# FPGA_ram.net
KiCad netlist of a schematic drawn in Altium Designer
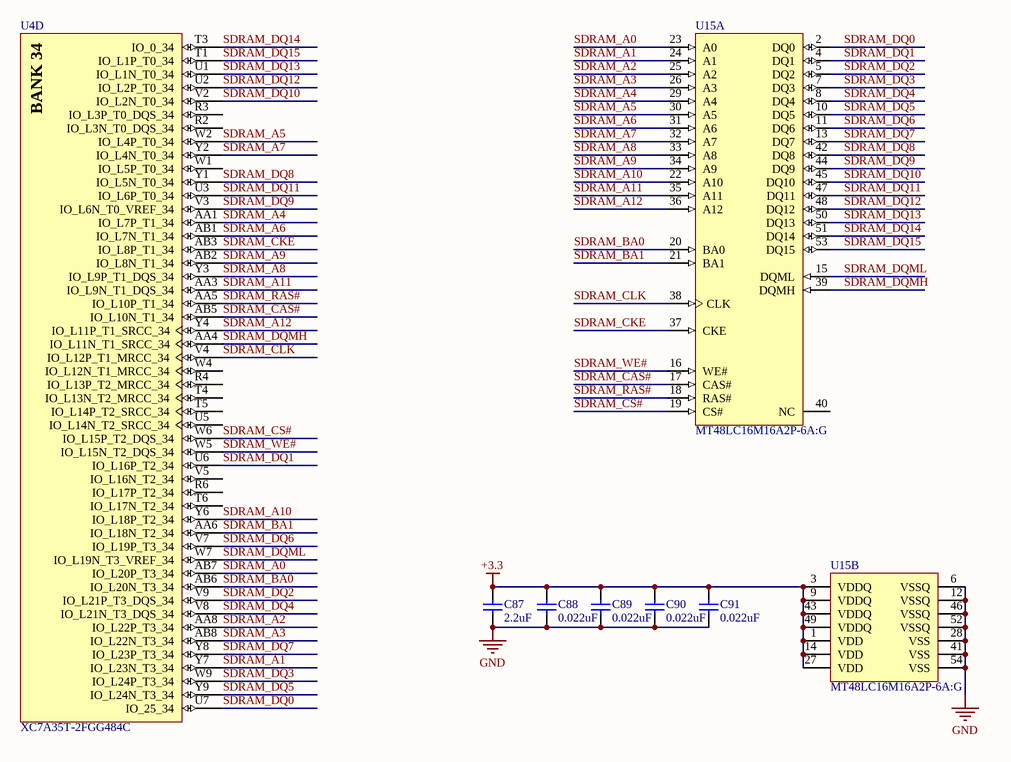
[diagram p0: FPGA ram.SchDoc]

(export (version "E")
  (design (tool "Eeschema 10.0.6"))
  (components
    (comp (ref "C87")
      (value "2.2uF")
      (footprint "CAPC1005X06L")
      (description "CAP CER 2.2UF 10V X5R 0402")
      (fields
        (field (name "PARTNUMBER") "GRM155R61A225KE95D")
        (field (name "DIGI-KEY PART NUMBER") "490-10451-1-ND")
      )
      (libsource (lib "cap_murata") (part "CAPACITOR"))
    )
    (comp (ref "C88")
      (value "0.022uF")
      (footprint "CAPC1005X06L")
      (description "CAP CER 0.022UF 10V X5R 0402")
      (fields
        (field (name "PARTNUMBER") "GRM155R61A223KA01D")
        (field (name "DIGI-KEY PART NUMBER") "490-6302-1-ND")
      )
      (libsource (lib "cap_murata") (part "CAPACITOR"))
    )
    (comp (ref "C89")
      (value "0.022uF")
      (footprint "CAPC1005X06L")
      (description "CAP CER 0.022UF 10V X5R 0402")
      (fields
        (field (name "PARTNUMBER") "GRM155R61A223KA01D")
        (field (name "DIGI-KEY PART NUMBER") "490-6302-1-ND")
      )
      (libsource (lib "cap_murata") (part "CAPACITOR"))
    )
    (comp (ref "C90")
      (value "0.022uF")
      (footprint "CAPC1005X06L")
      (description "CAP CER 0.022UF 10V X5R 0402")
      (fields
        (field (name "PARTNUMBER") "GRM155R61A223KA01D")
        (field (name "DIGI-KEY PART NUMBER") "490-6302-1-ND")
      )
      (libsource (lib "cap_murata") (part "CAPACITOR"))
    )
    (comp (ref "C91")
      (value "0.022uF")
      (footprint "CAPC1005X06L")
      (description "CAP CER 0.022UF 10V X5R 0402")
      (fields
        (field (name "PARTNUMBER") "GRM155R61A223KA01D")
        (field (name "DIGI-KEY PART NUMBER") "490-6302-1-ND")
      )
      (libsource (lib "cap_murata") (part "CAPACITOR"))
    )
    (comp (ref "U4")
      (value "XC7A35T-2FGG484C")
      (footprint "FGG484")
      (description "Artix-7 FPGA, 250 User I/Os, 4 GTP, 484-Ball BGA, Speed Grade 2, Commercial Grade, Pb-Free")
      (fields (field (name "MANUFACTURER") "Xilinx"))
      (libsource (lib "Altium Content Vault") (part "XLNX-XC7A35T-FGG484"))
    )
    (comp (ref "U15")
      (value "MT48LC16M16A2P-6A:G")
      (footprint "MICT-TG-54_M")
      (description "256 Mb PC133 SDR SDRAM, 16 Mb x 16, 3 to 3.6 V, 0 to 70 degC, 54-Pin TSOP (TG), Pb-Free")
      (fields (field (name "MANUFACTURER") "Micron"))
      (libsource (lib "Altium Content Vault") (part "MICT-MT48LC16M16A2P-54"))
    )
  )
  (nets
    (net (code "1") (name "+3.3") (class "Default")
      (node (ref "C87") (pin "1") (pinfunction "1_1") (pintype "passive"))
      (node (ref "C88") (pin "1") (pinfunction "1_1") (pintype "passive"))
      (node (ref "C89") (pin "1") (pinfunction "1_1") (pintype "passive"))
      (node (ref "C90") (pin "1") (pinfunction "1_1") (pintype "passive"))
      (node (ref "C91") (pin "1") (pinfunction "1_1") (pintype "passive"))
      (node (ref "U15") (pin "1") (pinfunction "VDD_1") (pintype "power_in"))
      (node (ref "U15") (pin "14") (pinfunction "VDD_14") (pintype "power_in"))
      (node (ref "U15") (pin "27") (pinfunction "VDD_27") (pintype "power_in"))
      (node (ref "U15") (pin "3") (pinfunction "VDDQ_3") (pintype "power_in"))
      (node (ref "U15") (pin "43") (pinfunction "VDDQ_43") (pintype "power_in"))
      (node (ref "U15") (pin "49") (pinfunction "VDDQ_49") (pintype "power_in"))
      (node (ref "U15") (pin "9") (pinfunction "VDDQ_9") (pintype "power_in"))
    )
    (net (code "2") (name "/SDRAM_A0") (class "Default")
      (node (ref "U15") (pin "23") (pinfunction "A0_23") (pintype "input"))
      (node (ref "U4") (pin "AB7") (pinfunction "IO_L20P_T3_34_AB7") (pintype "bidirectional"))
    )
    (net (code "3") (name "/SDRAM_A1") (class "Default")
      (node (ref "U15") (pin "24") (pinfunction "A1_24") (pintype "input"))
      (node (ref "U4") (pin "Y7") (pinfunction "IO_L23N_T3_34_Y7") (pintype "bidirectional"))
    )
    (net (code "4") (name "/SDRAM_A2") (class "Default")
      (node (ref "U15") (pin "25") (pinfunction "A2_25") (pintype "input"))
      (node (ref "U4") (pin "AA8") (pinfunction "IO_L22P_T3_34_AA8") (pintype "bidirectional"))
    )
    (net (code "5") (name "/SDRAM_A3") (class "Default")
      (node (ref "U15") (pin "26") (pinfunction "A3_26") (pintype "input"))
      (node (ref "U4") (pin "AB8") (pinfunction "IO_L22N_T3_34_AB8") (pintype "bidirectional"))
    )
    (net (code "6") (name "/SDRAM_A4") (class "Default")
      (node (ref "U15") (pin "29") (pinfunction "A4_29") (pintype "input"))
      (node (ref "U4") (pin "AA1") (pinfunction "IO_L7P_T1_34_AA1") (pintype "bidirectional"))
    )
    (net (code "7") (name "/SDRAM_A5") (class "Default")
      (node (ref "U15") (pin "30") (pinfunction "A5_30") (pintype "input"))
      (node (ref "U4") (pin "W2") (pinfunction "IO_L4P_T0_34_W2") (pintype "bidirectional"))
    )
    (net (code "8") (name "/SDRAM_A6") (class "Default")
      (node (ref "U15") (pin "31") (pinfunction "A6_31") (pintype "input"))
      (node (ref "U4") (pin "AB1") (pinfunction "IO_L7N_T1_34_AB1") (pintype "bidirectional"))
    )
    (net (code "9") (name "/SDRAM_A7") (class "Default")
      (node (ref "U15") (pin "32") (pinfunction "A7_32") (pintype "input"))
      (node (ref "U4") (pin "Y2") (pinfunction "IO_L4N_T0_34_Y2") (pintype "bidirectional"))
    )
    (net (code "10") (name "/SDRAM_A8") (class "Default")
      (node (ref "U15") (pin "33") (pinfunction "A8_33") (pintype "input"))
      (node (ref "U4") (pin "Y3") (pinfunction "IO_L9P_T1_DQS_34_Y3") (pintype "bidirectional"))
    )
    (net (code "11") (name "/SDRAM_A9") (class "Default")
      (node (ref "U15") (pin "34") (pinfunction "A9_34") (pintype "input"))
      (node (ref "U4") (pin "AB2") (pinfunction "IO_L8N_T1_34_AB2") (pintype "bidirectional"))
    )
    (net (code "12") (name "/SDRAM_A10") (class "Default")
      (node (ref "U15") (pin "22") (pinfunction "A10_22") (pintype "input"))
      (node (ref "U4") (pin "Y6") (pinfunction "IO_L18P_T2_34_Y6") (pintype "bidirectional"))
    )
    (net (code "13") (name "/SDRAM_A11") (class "Default")
      (node (ref "U15") (pin "35") (pinfunction "A11_35") (pintype "input"))
      (node (ref "U4") (pin "AA3") (pinfunction "IO_L9N_T1_DQS_34_AA3") (pintype "bidirectional"))
    )
    (net (code "14") (name "/SDRAM_A12") (class "Default")
      (node (ref "U15") (pin "36") (pinfunction "A12_36") (pintype "input"))
      (node (ref "U4") (pin "Y4") (pinfunction "IO_L11P_T1_SRCC_34_Y4") (pintype "bidirectional"))
    )
    (net (code "15") (name "/SDRAM_BA0") (class "Default")
      (node (ref "U15") (pin "20") (pinfunction "BA0_20") (pintype "input"))
      (node (ref "U4") (pin "AB6") (pinfunction "IO_L20N_T3_34_AB6") (pintype "bidirectional"))
    )
    (net (code "16") (name "/SDRAM_BA1") (class "Default")
      (node (ref "U15") (pin "21") (pinfunction "BA1_21") (pintype "input"))
      (node (ref "U4") (pin "AA6") (pinfunction "IO_L18N_T2_34_AA6") (pintype "bidirectional"))
    )
    (net (code "17") (name "/SDRAM_CAS#") (class "Default")
      (node (ref "U15") (pin "17") (pinfunction "CAS#_17") (pintype "input"))
      (node (ref "U4") (pin "AB5") (pinfunction "IO_L10N_T1_34_AB5") (pintype "bidirectional"))
    )
    (net (code "18") (name "/SDRAM_CKE") (class "Default")
      (node (ref "U15") (pin "37") (pinfunction "CKE_37") (pintype "input"))
      (node (ref "U4") (pin "AB3") (pinfunction "IO_L8P_T1_34_AB3") (pintype "bidirectional"))
    )
    (net (code "19") (name "/SDRAM_CLK") (class "Default")
      (node (ref "U15") (pin "38") (pinfunction "CLK_38") (pintype "input"))
      (node (ref "U4") (pin "V4") (pinfunction "IO_L12P_T1_MRCC_34_V4") (pintype "bidirectional"))
    )
    (net (code "20") (name "/SDRAM_CS#") (class "Default")
      (node (ref "U15") (pin "19") (pinfunction "CS#_19") (pintype "input"))
      (node (ref "U4") (pin "W6") (pinfunction "IO_L15P_T2_DQS_34_W6") (pintype "bidirectional"))
    )
    (net (code "21") (name "/SDRAM_DQ0") (class "Default")
      (node (ref "U15") (pin "2") (pinfunction "DQ0_2") (pintype "bidirectional"))
      (node (ref "U4") (pin "U7") (pinfunction "IO_25_34_U7") (pintype "bidirectional"))
    )
    (net (code "22") (name "/SDRAM_DQ1") (class "Default")
      (node (ref "U15") (pin "4") (pinfunction "DQ1_4") (pintype "bidirectional"))
      (node (ref "U4") (pin "U6") (pinfunction "IO_L16P_T2_34_U6") (pintype "bidirectional"))
    )
    (net (code "23") (name "/SDRAM_DQ2") (class "Default")
      (node (ref "U15") (pin "5") (pinfunction "DQ2_5") (pintype "bidirectional"))
      (node (ref "U4") (pin "V9") (pinfunction "IO_L21P_T3_DQS_34_V9") (pintype "bidirectional"))
    )
    (net (code "24") (name "/SDRAM_DQ3") (class "Default")
      (node (ref "U15") (pin "7") (pinfunction "DQ3_7") (pintype "bidirectional"))
      (node (ref "U4") (pin "W9") (pinfunction "IO_L24P_T3_34_W9") (pintype "bidirectional"))
    )
    (net (code "25") (name "/SDRAM_DQ4") (class "Default")
      (node (ref "U15") (pin "8") (pinfunction "DQ4_8") (pintype "bidirectional"))
      (node (ref "U4") (pin "V8") (pinfunction "IO_L21N_T3_DQS_34_V8") (pintype "bidirectional"))
    )
    (net (code "26") (name "/SDRAM_DQ5") (class "Default")
      (node (ref "U15") (pin "10") (pinfunction "DQ5_10") (pintype "bidirectional"))
      (node (ref "U4") (pin "Y9") (pinfunction "IO_L24N_T3_34_Y9") (pintype "bidirectional"))
    )
    (net (code "27") (name "/SDRAM_DQ6") (class "Default")
      (node (ref "U15") (pin "11") (pinfunction "DQ6_11") (pintype "bidirectional"))
      (node (ref "U4") (pin "V7") (pinfunction "IO_L19P_T3_34_V7") (pintype "bidirectional"))
    )
    (net (code "28") (name "/SDRAM_DQ7") (class "Default")
      (node (ref "U15") (pin "13") (pinfunction "DQ7_13") (pintype "bidirectional"))
      (node (ref "U4") (pin "Y8") (pinfunction "IO_L23P_T3_34_Y8") (pintype "bidirectional"))
    )
    (net (code "29") (name "/SDRAM_DQ8") (class "Default")
      (node (ref "U15") (pin "42") (pinfunction "DQ8_42") (pintype "bidirectional"))
      (node (ref "U4") (pin "Y1") (pinfunction "IO_L5N_T0_34_Y1") (pintype "bidirectional"))
    )
    (net (code "30") (name "/SDRAM_DQ9") (class "Default")
      (node (ref "U15") (pin "44") (pinfunction "DQ9_44") (pintype "bidirectional"))
      (node (ref "U4") (pin "V3") (pinfunction "IO_L6N_T0_VREF_34_V3") (pintype "bidirectional"))
    )
    (net (code "31") (name "/SDRAM_DQ10") (class "Default")
      (node (ref "U15") (pin "45") (pinfunction "DQ10_45") (pintype "bidirectional"))
      (node (ref "U4") (pin "V2") (pinfunction "IO_L2N_T0_34_V2") (pintype "bidirectional"))
    )
    (net (code "32") (name "/SDRAM_DQ11") (class "Default")
      (node (ref "U15") (pin "47") (pinfunction "DQ11_47") (pintype "bidirectional"))
      (node (ref "U4") (pin "U3") (pinfunction "IO_L6P_T0_34_U3") (pintype "bidirectional"))
    )
    (net (code "33") (name "/SDRAM_DQ12") (class "Default")
      (node (ref "U15") (pin "48") (pinfunction "DQ12_48") (pintype "bidirectional"))
      (node (ref "U4") (pin "U2") (pinfunction "IO_L2P_T0_34_U2") (pintype "bidirectional"))
    )
    (net (code "34") (name "/SDRAM_DQ13") (class "Default")
      (node (ref "U15") (pin "50") (pinfunction "DQ13_50") (pintype "bidirectional"))
      (node (ref "U4") (pin "U1") (pinfunction "IO_L1N_T0_34_U1") (pintype "bidirectional"))
    )
    (net (code "35") (name "/SDRAM_DQ14") (class "Default")
      (node (ref "U15") (pin "51") (pinfunction "DQ14_51") (pintype "bidirectional"))
      (node (ref "U4") (pin "T3") (pinfunction "IO_0_34_T3") (pintype "bidirectional"))
    )
    (net (code "36") (name "/SDRAM_DQ15") (class "Default")
      (node (ref "U15") (pin "53") (pinfunction "DQ15_53") (pintype "bidirectional"))
      (node (ref "U4") (pin "T1") (pinfunction "IO_L1P_T0_34_T1") (pintype "bidirectional"))
    )
    (net (code "37") (name "/SDRAM_DQMH") (class "Default")
      (node (ref "U15") (pin "39") (pinfunction "DQMH_39") (pintype "input"))
      (node (ref "U4") (pin "AA4") (pinfunction "IO_L11N_T1_SRCC_34_AA4") (pintype "bidirectional"))
    )
    (net (code "38") (name "/SDRAM_DQML") (class "Default")
      (node (ref "U15") (pin "15") (pinfunction "DQML_15") (pintype "input"))
      (node (ref "U4") (pin "W7") (pinfunction "IO_L19N_T3_VREF_34_W7") (pintype "bidirectional"))
    )
    (net (code "39") (name "/SDRAM_RAS#") (class "Default")
      (node (ref "U15") (pin "18") (pinfunction "RAS#_18") (pintype "input"))
      (node (ref "U4") (pin "AA5") (pinfunction "IO_L10P_T1_34_AA5") (pintype "bidirectional"))
    )
    (net (code "40") (name "/SDRAM_WE#") (class "Default")
      (node (ref "U15") (pin "16") (pinfunction "WE#_16") (pintype "input"))
      (node (ref "U4") (pin "W5") (pinfunction "IO_L15N_T2_DQS_34_W5") (pintype "bidirectional"))
    )
    (net (code "41") (name "GND") (class "Default")
      (node (ref "C87") (pin "2") (pinfunction "2_2") (pintype "passive"))
      (node (ref "C88") (pin "2") (pinfunction "2_2") (pintype "passive"))
      (node (ref "C89") (pin "2") (pinfunction "2_2") (pintype "passive"))
      (node (ref "C90") (pin "2") (pinfunction "2_2") (pintype "passive"))
      (node (ref "C91") (pin "2") (pinfunction "2_2") (pintype "passive"))
      (node (ref "U15") (pin "12") (pinfunction "VSSQ_12") (pintype "power_in"))
      (node (ref "U15") (pin "28") (pinfunction "VSS_28") (pintype "power_in"))
      (node (ref "U15") (pin "41") (pinfunction "VSS_41") (pintype "power_in"))
      (node (ref "U15") (pin "46") (pinfunction "VSSQ_46") (pintype "power_in"))
      (node (ref "U15") (pin "52") (pinfunction "VSSQ_52") (pintype "power_in"))
      (node (ref "U15") (pin "54") (pinfunction "VSS_54") (pintype "power_in"))
      (node (ref "U15") (pin "6") (pinfunction "VSSQ_6") (pintype "power_in"))
    )
    (net (code "42") (name "unconnected-(U4D-IO_L3N_T0_DQS_34-PadR2)") (class "Default")
      (node (ref "U4") (pin "R2") (pinfunction "IO_L3N_T0_DQS_34_R2") (pintype "bidirectional"))
    )
    (net (code "43") (name "unconnected-(U4D-IO_L3P_T0_DQS_34-PadR3)") (class "Default")
      (node (ref "U4") (pin "R3") (pinfunction "IO_L3P_T0_DQS_34_R3") (pintype "bidirectional"))
    )
    (net (code "44") (name "unconnected-(U4D-IO_L5P_T0_34-PadW1)") (class "Default")
      (node (ref "U4") (pin "W1") (pinfunction "IO_L5P_T0_34_W1") (pintype "bidirectional"))
    )
    (net (code "45") (name "unconnected-(U4D-IO_L12N_T1_MRCC_34-PadW4)") (class "Default")
      (node (ref "U4") (pin "W4") (pinfunction "IO_L12N_T1_MRCC_34_W4") (pintype "bidirectional"))
    )
    (net (code "46") (name "unconnected-(U4D-IO_L13N_T2_MRCC_34-PadT4)") (class "Default")
      (node (ref "U4") (pin "T4") (pinfunction "IO_L13N_T2_MRCC_34_T4") (pintype "bidirectional"))
    )
    (net (code "47") (name "unconnected-(U4D-IO_L13P_T2_MRCC_34-PadR4)") (class "Default")
      (node (ref "U4") (pin "R4") (pinfunction "IO_L13P_T2_MRCC_34_R4") (pintype "bidirectional"))
    )
    (net (code "48") (name "unconnected-(U4D-IO_L14N_T2_SRCC_34-PadU5)") (class "Default")
      (node (ref "U4") (pin "U5") (pinfunction "IO_L14N_T2_SRCC_34_U5") (pintype "bidirectional"))
    )
    (net (code "49") (name "unconnected-(U4D-IO_L14P_T2_SRCC_34-PadT5)") (class "Default")
      (node (ref "U4") (pin "T5") (pinfunction "IO_L14P_T2_SRCC_34_T5") (pintype "bidirectional"))
    )
    (net (code "50") (name "unconnected-(U4D-IO_L16N_T2_34-PadV5)") (class "Default")
      (node (ref "U4") (pin "V5") (pinfunction "IO_L16N_T2_34_V5") (pintype "bidirectional"))
    )
    (net (code "51") (name "unconnected-(U4D-IO_L17N_T2_34-PadT6)") (class "Default")
      (node (ref "U4") (pin "T6") (pinfunction "IO_L17N_T2_34_T6") (pintype "bidirectional"))
    )
    (net (code "52") (name "unconnected-(U4D-IO_L17P_T2_34-PadR6)") (class "Default")
      (node (ref "U4") (pin "R6") (pinfunction "IO_L17P_T2_34_R6") (pintype "bidirectional"))
    )
    (net (code "53") (name "unconnected-(U15A-NC-Pad40)") (class "Default")
      (node (ref "U15") (pin "40") (pinfunction "NC_40") (pintype "passive"))
    )
  )
)
